# pcb_v2_3.net
KiCad netlist of a schematic drawn in EAGLE
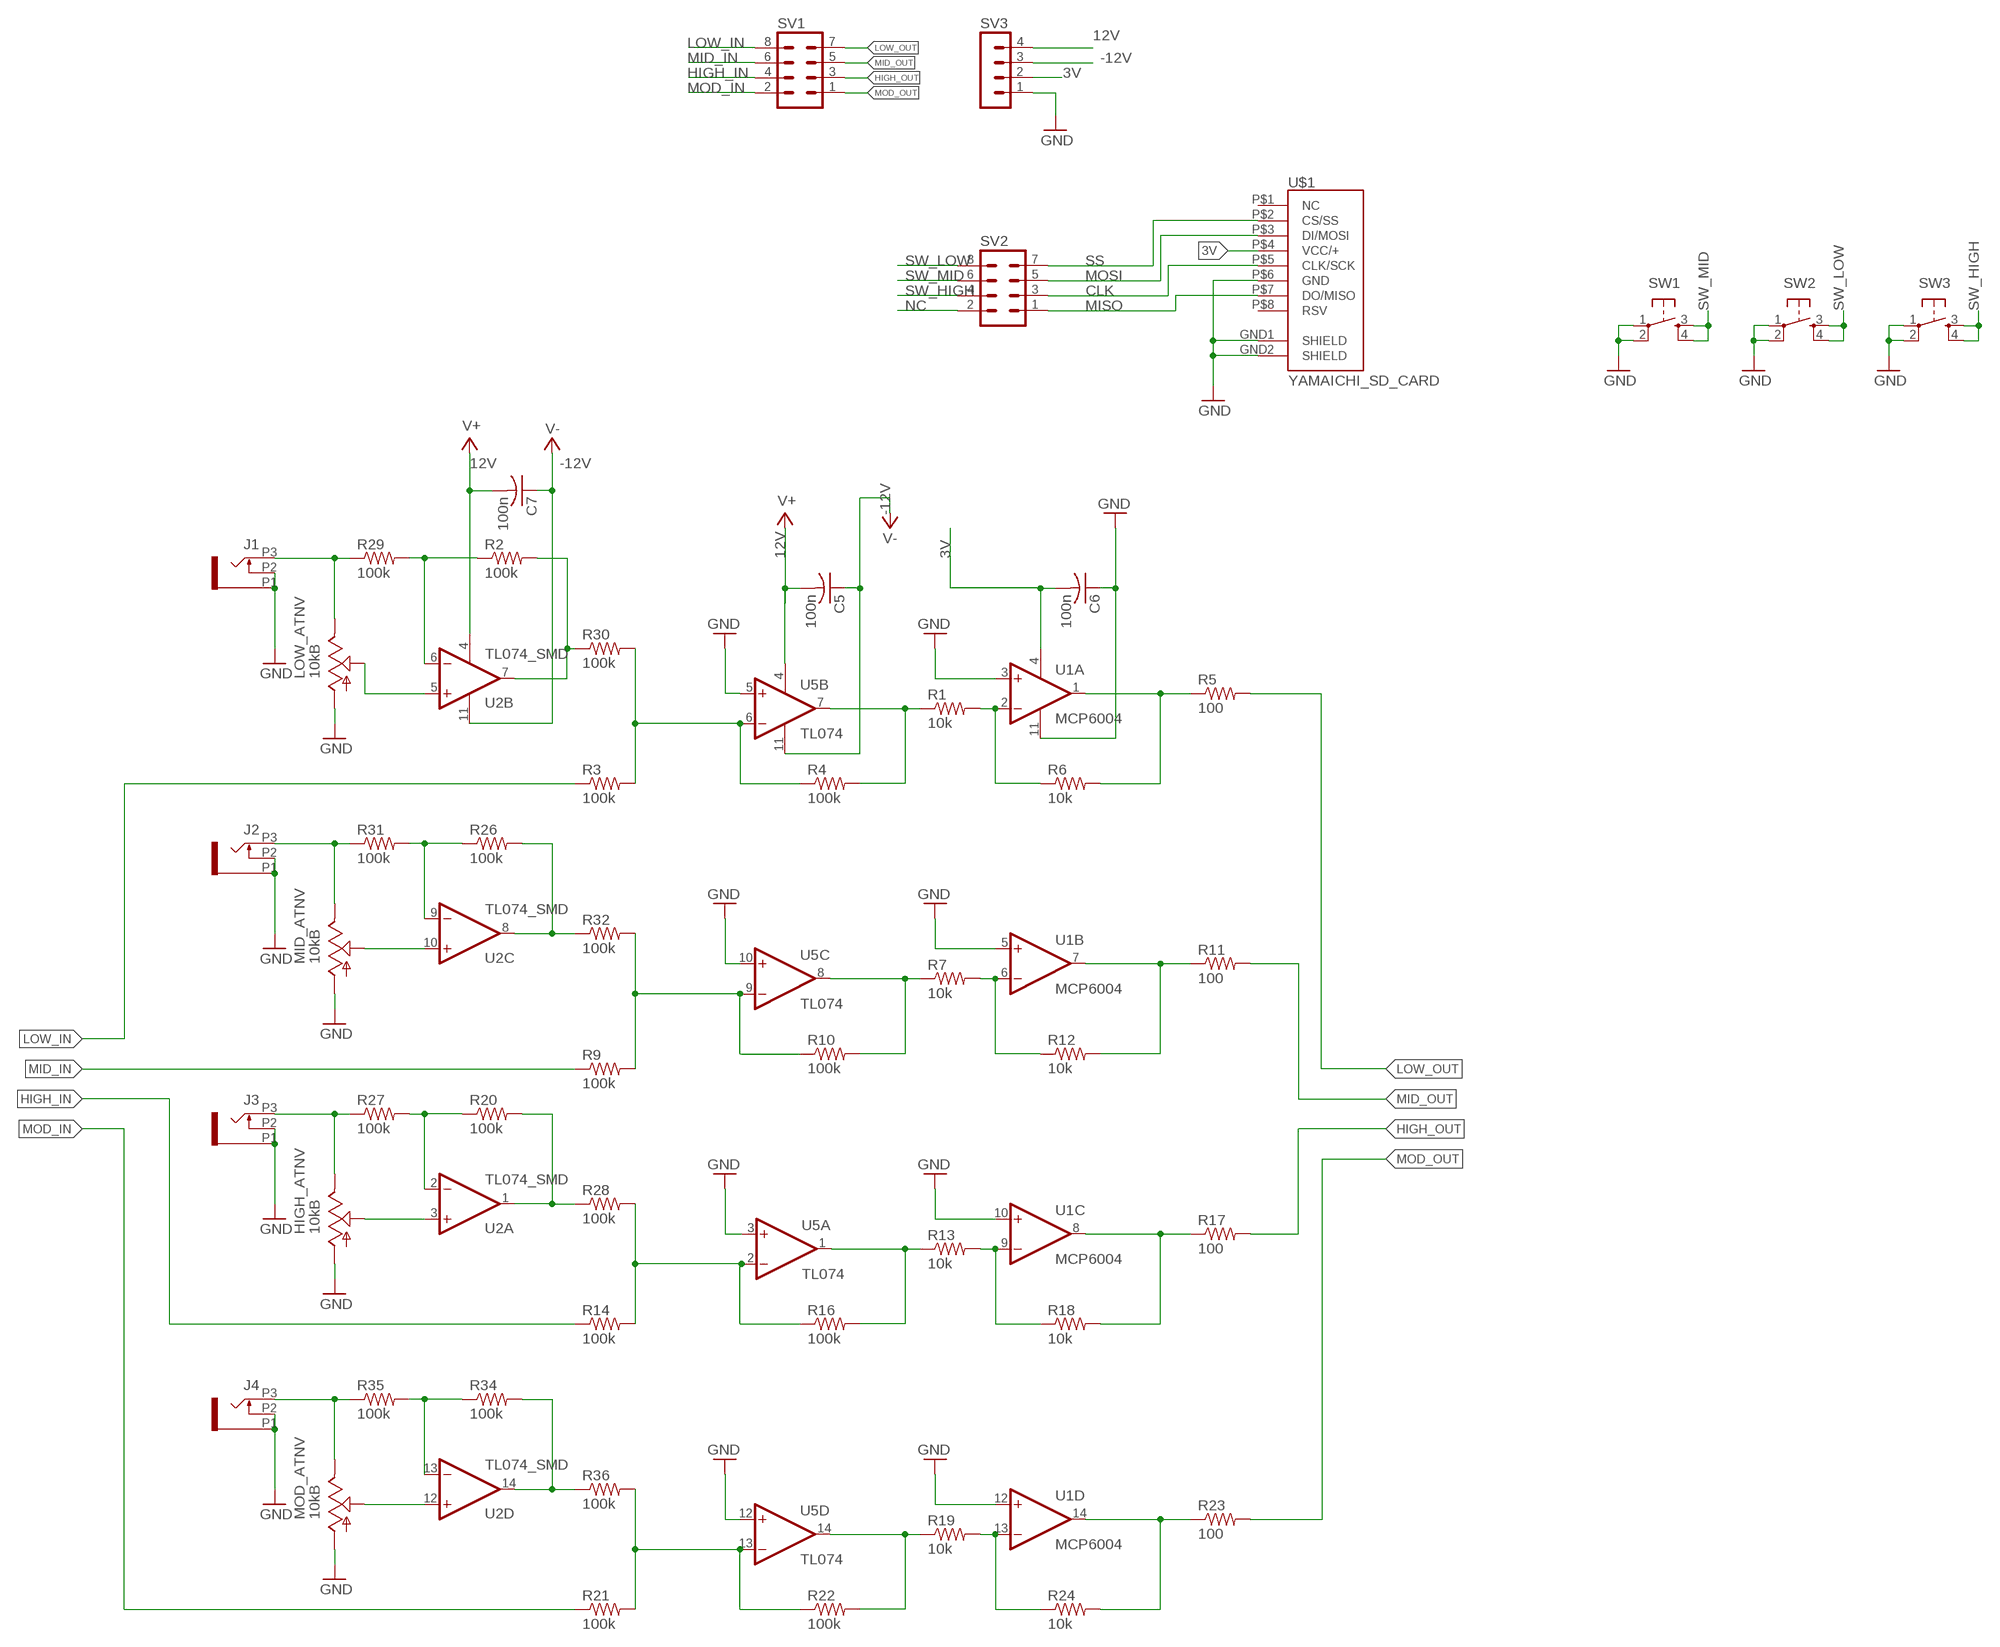
[diagram p0: schematic, sheet 1]

(export (version "E")
  (design (tool "Eeschema 10.0.6"))
  (components
    (comp (ref "C5")
      (value "100n")
      (footprint "eagle-import:C0603")
      (fields (field (name "SPICEPREFIX") "C"))
      (libsource (lib "eagle-import") (part "C-USC0603"))
    )
    (comp (ref "C6")
      (value "100n")
      (footprint "eagle-import:C0603")
      (fields (field (name "SPICEPREFIX") "C"))
      (libsource (lib "eagle-import") (part "C-USC0603"))
    )
    (comp (ref "C7")
      (value "100n")
      (footprint "eagle-import:C0603")
      (fields (field (name "SPICEPREFIX") "C"))
      (libsource (lib "eagle-import") (part "C-USC0603"))
    )
    (comp (ref "HIGH_ATNV")
      (value "10kB")
      (footprint "eagle-import:ALPS_POT_VERTICAL")
      (libsource (lib "eagle-import") (part "POT_USVERTICAL"))
    )
    (comp (ref "J1")
      (value "PJ301_THONKICONN6")
      (footprint "eagle-import:WQP_PJ_301M6")
      (fields (field (name "SPICEPREFIX") "J"))
      (libsource (lib "eagle-import") (part "PJ301_THONKICONN6"))
    )
    (comp (ref "J2")
      (value "PJ301_THONKICONN6")
      (footprint "eagle-import:WQP_PJ_301M6")
      (fields (field (name "SPICEPREFIX") "J"))
      (libsource (lib "eagle-import") (part "PJ301_THONKICONN6"))
    )
    (comp (ref "J3")
      (value "PJ301_THONKICONN6")
      (footprint "eagle-import:WQP_PJ_301M6")
      (fields (field (name "SPICEPREFIX") "J"))
      (libsource (lib "eagle-import") (part "PJ301_THONKICONN6"))
    )
    (comp (ref "J4")
      (value "PJ301_THONKICONN6")
      (footprint "eagle-import:WQP_PJ_301M6")
      (fields (field (name "SPICEPREFIX") "J"))
      (libsource (lib "eagle-import") (part "PJ301_THONKICONN6"))
    )
    (comp (ref "LOW_ATNV")
      (value "10kB")
      (footprint "eagle-import:ALPS_POT_VERTICAL")
      (libsource (lib "eagle-import") (part "POT_USVERTICAL"))
    )
    (comp (ref "MID_ATNV")
      (value "10kB")
      (footprint "eagle-import:ALPS_POT_VERTICAL")
      (libsource (lib "eagle-import") (part "POT_USVERTICAL"))
    )
    (comp (ref "MOD_ATNV")
      (value "10kB")
      (footprint "eagle-import:ALPS_POT_VERTICAL")
      (libsource (lib "eagle-import") (part "POT_USVERTICAL"))
    )
    (comp (ref "R1")
      (value "10k")
      (footprint "eagle-import:R0603")
      (fields (field (name "SPICEPREFIX") "R"))
      (libsource (lib "eagle-import") (part "R-US_R0603"))
    )
    (comp (ref "R2")
      (value "100k")
      (footprint "eagle-import:R0603")
      (fields (field (name "SPICEPREFIX") "R"))
      (libsource (lib "eagle-import") (part "R-US_R0603"))
    )
    (comp (ref "R3")
      (value "100k")
      (footprint "eagle-import:R0603")
      (fields (field (name "SPICEPREFIX") "R"))
      (libsource (lib "eagle-import") (part "R-US_R0603"))
    )
    (comp (ref "R4")
      (value "100k")
      (footprint "eagle-import:R0603")
      (fields (field (name "SPICEPREFIX") "R"))
      (libsource (lib "eagle-import") (part "R-US_R0603"))
    )
    (comp (ref "R5")
      (value "100")
      (footprint "eagle-import:R0603")
      (fields (field (name "SPICEPREFIX") "R"))
      (libsource (lib "eagle-import") (part "R-US_R0603"))
    )
    (comp (ref "R6")
      (value "10k")
      (footprint "eagle-import:R0603")
      (fields (field (name "SPICEPREFIX") "R"))
      (libsource (lib "eagle-import") (part "R-US_R0603"))
    )
    (comp (ref "R7")
      (value "10k")
      (footprint "eagle-import:R0603")
      (fields (field (name "SPICEPREFIX") "R"))
      (libsource (lib "eagle-import") (part "R-US_R0603"))
    )
    (comp (ref "R9")
      (value "100k")
      (footprint "eagle-import:R0603")
      (fields (field (name "SPICEPREFIX") "R"))
      (libsource (lib "eagle-import") (part "R-US_R0603"))
    )
    (comp (ref "R10")
      (value "100k")
      (footprint "eagle-import:R0603")
      (fields (field (name "SPICEPREFIX") "R"))
      (libsource (lib "eagle-import") (part "R-US_R0603"))
    )
    (comp (ref "R11")
      (value "100")
      (footprint "eagle-import:R0603")
      (fields (field (name "SPICEPREFIX") "R"))
      (libsource (lib "eagle-import") (part "R-US_R0603"))
    )
    (comp (ref "R12")
      (value "10k")
      (footprint "eagle-import:R0603")
      (fields (field (name "SPICEPREFIX") "R"))
      (libsource (lib "eagle-import") (part "R-US_R0603"))
    )
    (comp (ref "R13")
      (value "10k")
      (footprint "eagle-import:R0603")
      (fields (field (name "SPICEPREFIX") "R"))
      (libsource (lib "eagle-import") (part "R-US_R0603"))
    )
    (comp (ref "R14")
      (value "100k")
      (footprint "eagle-import:R0603")
      (fields (field (name "SPICEPREFIX") "R"))
      (libsource (lib "eagle-import") (part "R-US_R0603"))
    )
    (comp (ref "R16")
      (value "100k")
      (footprint "eagle-import:R0603")
      (fields (field (name "SPICEPREFIX") "R"))
      (libsource (lib "eagle-import") (part "R-US_R0603"))
    )
    (comp (ref "R17")
      (value "100")
      (footprint "eagle-import:R0603")
      (fields (field (name "SPICEPREFIX") "R"))
      (libsource (lib "eagle-import") (part "R-US_R0603"))
    )
    (comp (ref "R18")
      (value "10k")
      (footprint "eagle-import:R0603")
      (fields (field (name "SPICEPREFIX") "R"))
      (libsource (lib "eagle-import") (part "R-US_R0603"))
    )
    (comp (ref "R19")
      (value "10k")
      (footprint "eagle-import:R0603")
      (fields (field (name "SPICEPREFIX") "R"))
      (libsource (lib "eagle-import") (part "R-US_R0603"))
    )
    (comp (ref "R20")
      (value "100k")
      (footprint "eagle-import:R0603")
      (fields (field (name "SPICEPREFIX") "R"))
      (libsource (lib "eagle-import") (part "R-US_R0603"))
    )
    (comp (ref "R21")
      (value "100k")
      (footprint "eagle-import:R0603")
      (fields (field (name "SPICEPREFIX") "R"))
      (libsource (lib "eagle-import") (part "R-US_R0603"))
    )
    (comp (ref "R22")
      (value "100k")
      (footprint "eagle-import:R0603")
      (fields (field (name "SPICEPREFIX") "R"))
      (libsource (lib "eagle-import") (part "R-US_R0603"))
    )
    (comp (ref "R23")
      (value "100")
      (footprint "eagle-import:R0603")
      (fields (field (name "SPICEPREFIX") "R"))
      (libsource (lib "eagle-import") (part "R-US_R0603"))
    )
    (comp (ref "R24")
      (value "10k")
      (footprint "eagle-import:R0603")
      (fields (field (name "SPICEPREFIX") "R"))
      (libsource (lib "eagle-import") (part "R-US_R0603"))
    )
    (comp (ref "R26")
      (value "100k")
      (footprint "eagle-import:R0603")
      (fields (field (name "SPICEPREFIX") "R"))
      (libsource (lib "eagle-import") (part "R-US_R0603"))
    )
    (comp (ref "R27")
      (value "100k")
      (footprint "eagle-import:R0603")
      (fields (field (name "SPICEPREFIX") "R"))
      (libsource (lib "eagle-import") (part "R-US_R0603"))
    )
    (comp (ref "R28")
      (value "100k")
      (footprint "eagle-import:R0603")
      (fields (field (name "SPICEPREFIX") "R"))
      (libsource (lib "eagle-import") (part "R-US_R0603"))
    )
    (comp (ref "R29")
      (value "100k")
      (footprint "eagle-import:R0603")
      (fields (field (name "SPICEPREFIX") "R"))
      (libsource (lib "eagle-import") (part "R-US_R0603"))
    )
    (comp (ref "R30")
      (value "100k")
      (footprint "eagle-import:R0603")
      (fields (field (name "SPICEPREFIX") "R"))
      (libsource (lib "eagle-import") (part "R-US_R0603"))
    )
    (comp (ref "R31")
      (value "100k")
      (footprint "eagle-import:R0603")
      (fields (field (name "SPICEPREFIX") "R"))
      (libsource (lib "eagle-import") (part "R-US_R0603"))
    )
    (comp (ref "R32")
      (value "100k")
      (footprint "eagle-import:R0603")
      (fields (field (name "SPICEPREFIX") "R"))
      (libsource (lib "eagle-import") (part "R-US_R0603"))
    )
    (comp (ref "R34")
      (value "100k")
      (footprint "eagle-import:R0603")
      (fields (field (name "SPICEPREFIX") "R"))
      (libsource (lib "eagle-import") (part "R-US_R0603"))
    )
    (comp (ref "R35")
      (value "100k")
      (footprint "eagle-import:R0603")
      (fields (field (name "SPICEPREFIX") "R"))
      (libsource (lib "eagle-import") (part "R-US_R0603"))
    )
    (comp (ref "R36")
      (value "100k")
      (footprint "eagle-import:R0603")
      (fields (field (name "SPICEPREFIX") "R"))
      (libsource (lib "eagle-import") (part "R-US_R0603"))
    )
    (comp (ref "SV1")
      (value "MA04-2")
      (footprint "eagle-import:MA04-2")
      (libsource (lib "eagle-import") (part "MA04-2"))
    )
    (comp (ref "SV2")
      (value "MA04-2")
      (footprint "eagle-import:MA04-2")
      (libsource (lib "eagle-import") (part "MA04-2"))
    )
    (comp (ref "SV3")
      (value "MA04-1")
      (footprint "eagle-import:MA04-1")
      (libsource (lib "eagle-import") (part "MA04-1"))
    )
    (comp (ref "SW1")
      (value "TAC_SWITCHPTH")
      (footprint "eagle-import:TACTILE-PTH")
      (libsource (lib "eagle-import") (part "TAC_SWITCHPTH"))
    )
    (comp (ref "SW2")
      (value "TAC_SWITCHPTH")
      (footprint "eagle-import:TACTILE-PTH")
      (libsource (lib "eagle-import") (part "TAC_SWITCHPTH"))
    )
    (comp (ref "SW3")
      (value "TAC_SWITCHPTH")
      (footprint "eagle-import:TACTILE-PTH")
      (libsource (lib "eagle-import") (part "TAC_SWITCHPTH"))
    )
    (comp (ref "U$1")
      (value "YAMAICHI_SD_CARD")
      (footprint "eagle-import:YAMAICHI_MICROSD_VERTICAL")
      (libsource (lib "eagle-import") (part "YAMAICHI_SD_CARD"))
    )
    (comp (ref "U1")
      (value "MCP6004")
      (footprint "eagle-import:SO14")
      (libsource (lib "eagle-import") (part "MCP6004_SMD"))
    )
    (comp (ref "U2")
      (value "TL074_SMD")
      (footprint "eagle-import:SO14")
      (libsource (lib "eagle-import") (part "TL074_SMD"))
    )
    (comp (ref "U5")
      (value "TL074")
      (footprint "eagle-import:SO14")
      (libsource (lib "eagle-import") (part "TL074_SMD"))
    )
  )
  (nets
    (net (code "1") (name "/CLK") (class "Default")
      (node (ref "SV2") (pin "3") (pinfunction "3_3") (pintype "passive"))
      (node (ref "U$1") (pin "P$5") (pinfunction "CLK/SCK_P$5") (pintype "bidirectional"))
    )
    (net (code "2") (name "/MISO") (class "Default")
      (node (ref "SV2") (pin "1") (pinfunction "1_1") (pintype "passive"))
      (node (ref "U$1") (pin "P$7") (pinfunction "DO/MISO_P$7") (pintype "bidirectional"))
    )
    (net (code "3") (name "/MOSI") (class "Default")
      (node (ref "SV2") (pin "5") (pinfunction "5_5") (pintype "passive"))
      (node (ref "U$1") (pin "P$3") (pinfunction "DI/MOSI_P$3") (pintype "bidirectional"))
    )
    (net (code "4") (name "/NC") (class "Default")
      (node (ref "SV2") (pin "2") (pinfunction "2_2") (pintype "passive"))
    )
    (net (code "5") (name "/SS") (class "Default")
      (node (ref "SV2") (pin "7") (pinfunction "7_7") (pintype "passive"))
      (node (ref "U$1") (pin "P$2") (pinfunction "CS/SS_P$2") (pintype "bidirectional"))
    )
    (net (code "6") (name "/SW_HIGH") (class "Default")
      (node (ref "SV2") (pin "4") (pinfunction "4_4") (pintype "passive"))
      (node (ref "SW3") (pin "3") (pinfunction "3_3") (pintype "passive"))
      (node (ref "SW3") (pin "4") (pinfunction "4_4") (pintype "passive"))
    )
    (net (code "7") (name "/SW_LOW") (class "Default")
      (node (ref "SV2") (pin "8") (pinfunction "8_8") (pintype "passive"))
      (node (ref "SW2") (pin "3") (pinfunction "3_3") (pintype "passive"))
      (node (ref "SW2") (pin "4") (pinfunction "4_4") (pintype "passive"))
    )
    (net (code "8") (name "/SW_MID") (class "Default")
      (node (ref "SV2") (pin "6") (pinfunction "6_6") (pintype "passive"))
      (node (ref "SW1") (pin "3") (pinfunction "3_3") (pintype "passive"))
      (node (ref "SW1") (pin "4") (pinfunction "4_4") (pintype "passive"))
    )
    (net (code "9") (name "3V") (class "Default")
      (node (ref "C6") (pin "2") (pinfunction "2_2") (pintype "passive"))
      (node (ref "SV3") (pin "2") (pinfunction "2_2") (pintype "passive"))
      (node (ref "U$1") (pin "P$4") (pinfunction "VCC/+_P$4") (pintype "bidirectional"))
      (node (ref "U1") (pin "4") (pinfunction "V+_4") (pintype "power_in"))
    )
    (net (code "10") (name "GND") (class "Default")
      (node (ref "C6") (pin "1") (pinfunction "1_1") (pintype "passive"))
      (node (ref "HIGH_ATNV") (pin "P$3") (pinfunction "A_P$3") (pintype "passive"))
      (node (ref "J1") (pin "P1") (pinfunction "1_P1") (pintype "passive"))
      (node (ref "J1") (pin "P2") (pinfunction "2_P2") (pintype "passive"))
      (node (ref "J2") (pin "P1") (pinfunction "1_P1") (pintype "passive"))
      (node (ref "J2") (pin "P2") (pinfunction "2_P2") (pintype "passive"))
      (node (ref "J3") (pin "P1") (pinfunction "1_P1") (pintype "passive"))
      (node (ref "J3") (pin "P2") (pinfunction "2_P2") (pintype "passive"))
      (node (ref "J4") (pin "P1") (pinfunction "1_P1") (pintype "passive"))
      (node (ref "J4") (pin "P2") (pinfunction "2_P2") (pintype "passive"))
      (node (ref "LOW_ATNV") (pin "P$3") (pinfunction "A_P$3") (pintype "passive"))
      (node (ref "MID_ATNV") (pin "P$3") (pinfunction "A_P$3") (pintype "passive"))
      (node (ref "MOD_ATNV") (pin "P$3") (pinfunction "A_P$3") (pintype "passive"))
      (node (ref "SV3") (pin "1") (pinfunction "1_1") (pintype "passive"))
      (node (ref "SW1") (pin "1") (pinfunction "1_1") (pintype "passive"))
      (node (ref "SW1") (pin "2") (pinfunction "2_2") (pintype "passive"))
      (node (ref "SW2") (pin "1") (pinfunction "1_1") (pintype "passive"))
      (node (ref "SW2") (pin "2") (pinfunction "2_2") (pintype "passive"))
      (node (ref "SW3") (pin "1") (pinfunction "1_1") (pintype "passive"))
      (node (ref "SW3") (pin "2") (pinfunction "2_2") (pintype "passive"))
      (node (ref "U$1") (pin "GND1") (pinfunction "SHIELD_GND1") (pintype "bidirectional"))
      (node (ref "U$1") (pin "GND2") (pinfunction "SHIELD_GND2") (pintype "bidirectional"))
      (node (ref "U$1") (pin "P$6") (pinfunction "GND_P$6") (pintype "bidirectional"))
      (node (ref "U1") (pin "10") (pinfunction "+IN_10") (pintype "input"))
      (node (ref "U1") (pin "11") (pinfunction "V-_11") (pintype "power_in"))
      (node (ref "U1") (pin "12") (pinfunction "+IN_12") (pintype "input"))
      (node (ref "U1") (pin "3") (pinfunction "+IN_3") (pintype "input"))
      (node (ref "U1") (pin "5") (pinfunction "+IN_5") (pintype "input"))
      (node (ref "U5") (pin "10") (pinfunction "+IN_10") (pintype "input"))
      (node (ref "U5") (pin "12") (pinfunction "+IN_12") (pintype "input"))
      (node (ref "U5") (pin "3") (pinfunction "+IN_3") (pintype "input"))
      (node (ref "U5") (pin "5") (pinfunction "+IN_5") (pintype "input"))
    )
    (net (code "11") (name "HIGH_IN") (class "Default")
      (node (ref "R14") (pin "1") (pinfunction "1_1") (pintype "passive"))
      (node (ref "SV1") (pin "4") (pinfunction "4_4") (pintype "passive"))
    )
    (net (code "12") (name "HIGH_OUT") (class "Default")
      (node (ref "R17") (pin "2") (pinfunction "2_2") (pintype "passive"))
      (node (ref "SV1") (pin "3") (pinfunction "3_3") (pintype "passive"))
    )
    (net (code "13") (name "LOW_IN") (class "Default")
      (node (ref "R3") (pin "1") (pinfunction "1_1") (pintype "passive"))
      (node (ref "SV1") (pin "8") (pinfunction "8_8") (pintype "passive"))
    )
    (net (code "14") (name "LOW_OUT") (class "Default")
      (node (ref "R5") (pin "2") (pinfunction "2_2") (pintype "passive"))
      (node (ref "SV1") (pin "7") (pinfunction "7_7") (pintype "passive"))
    )
    (net (code "15") (name "MID_IN") (class "Default")
      (node (ref "R9") (pin "1") (pinfunction "1_1") (pintype "passive"))
      (node (ref "SV1") (pin "6") (pinfunction "6_6") (pintype "passive"))
    )
    (net (code "16") (name "MID_OUT") (class "Default")
      (node (ref "R11") (pin "2") (pinfunction "2_2") (pintype "passive"))
      (node (ref "SV1") (pin "5") (pinfunction "5_5") (pintype "passive"))
    )
    (net (code "17") (name "MOD_IN") (class "Default")
      (node (ref "R21") (pin "1") (pinfunction "1_1") (pintype "passive"))
      (node (ref "SV1") (pin "2") (pinfunction "2_2") (pintype "passive"))
    )
    (net (code "18") (name "MOD_OUT") (class "Default")
      (node (ref "R23") (pin "2") (pinfunction "2_2") (pintype "passive"))
      (node (ref "SV1") (pin "1") (pinfunction "1_1") (pintype "passive"))
    )
    (net (code "19") (name "Net-(HIGH_ATNV-E)") (class "Default")
      (node (ref "HIGH_ATNV") (pin "P$1") (pinfunction "E_P$1") (pintype "passive"))
      (node (ref "J3") (pin "P3") (pinfunction "3_P3") (pintype "passive"))
      (node (ref "R27") (pin "1") (pinfunction "1_1") (pintype "passive"))
    )
    (net (code "20") (name "Net-(HIGH_ATNV-S)") (class "Default")
      (node (ref "HIGH_ATNV") (pin "P$2") (pinfunction "S_P$2") (pintype "passive"))
      (node (ref "U2") (pin "3") (pinfunction "+IN_3") (pintype "input"))
    )
    (net (code "21") (name "Net-(J1-3)") (class "Default")
      (node (ref "J1") (pin "P3") (pinfunction "3_P3") (pintype "passive"))
      (node (ref "LOW_ATNV") (pin "P$1") (pinfunction "E_P$1") (pintype "passive"))
      (node (ref "R29") (pin "1") (pinfunction "1_1") (pintype "passive"))
    )
    (net (code "22") (name "Net-(J2-3)") (class "Default")
      (node (ref "J2") (pin "P3") (pinfunction "3_P3") (pintype "passive"))
      (node (ref "MID_ATNV") (pin "P$1") (pinfunction "E_P$1") (pintype "passive"))
      (node (ref "R31") (pin "1") (pinfunction "1_1") (pintype "passive"))
    )
    (net (code "23") (name "Net-(J4-3)") (class "Default")
      (node (ref "J4") (pin "P3") (pinfunction "3_P3") (pintype "passive"))
      (node (ref "MOD_ATNV") (pin "P$1") (pinfunction "E_P$1") (pintype "passive"))
      (node (ref "R35") (pin "1") (pinfunction "1_1") (pintype "passive"))
    )
    (net (code "24") (name "Net-(LOW_ATNV-S)") (class "Default")
      (node (ref "LOW_ATNV") (pin "P$2") (pinfunction "S_P$2") (pintype "passive"))
      (node (ref "U2") (pin "5") (pinfunction "+IN_5") (pintype "input"))
    )
    (net (code "25") (name "Net-(MID_ATNV-S)") (class "Default")
      (node (ref "MID_ATNV") (pin "P$2") (pinfunction "S_P$2") (pintype "passive"))
      (node (ref "U2") (pin "10") (pinfunction "+IN_10") (pintype "input"))
    )
    (net (code "26") (name "Net-(MOD_ATNV-S)") (class "Default")
      (node (ref "MOD_ATNV") (pin "P$2") (pinfunction "S_P$2") (pintype "passive"))
      (node (ref "U2") (pin "12") (pinfunction "+IN_12") (pintype "input"))
    )
    (net (code "27") (name "Net-(U1A--IN)") (class "Default")
      (node (ref "R1") (pin "2") (pinfunction "2_2") (pintype "passive"))
      (node (ref "R6") (pin "1") (pinfunction "1_1") (pintype "passive"))
      (node (ref "U1") (pin "2") (pinfunction "-IN_2") (pintype "input"))
    )
    (net (code "28") (name "Net-(U1A-OUT)") (class "Default")
      (node (ref "R5") (pin "1") (pinfunction "1_1") (pintype "passive"))
      (node (ref "R6") (pin "2") (pinfunction "2_2") (pintype "passive"))
      (node (ref "U1") (pin "1") (pinfunction "OUT_1") (pintype "output"))
    )
    (net (code "29") (name "Net-(U1B--IN)") (class "Default")
      (node (ref "R12") (pin "1") (pinfunction "1_1") (pintype "passive"))
      (node (ref "R7") (pin "2") (pinfunction "2_2") (pintype "passive"))
      (node (ref "U1") (pin "6") (pinfunction "-IN_6") (pintype "input"))
    )
    (net (code "30") (name "Net-(U1B-OUT)") (class "Default")
      (node (ref "R11") (pin "1") (pinfunction "1_1") (pintype "passive"))
      (node (ref "R12") (pin "2") (pinfunction "2_2") (pintype "passive"))
      (node (ref "U1") (pin "7") (pinfunction "OUT_7") (pintype "output"))
    )
    (net (code "31") (name "Net-(U1C--IN)") (class "Default")
      (node (ref "R13") (pin "2") (pinfunction "2_2") (pintype "passive"))
      (node (ref "R18") (pin "1") (pinfunction "1_1") (pintype "passive"))
      (node (ref "U1") (pin "9") (pinfunction "-IN_9") (pintype "input"))
    )
    (net (code "32") (name "Net-(U1C-OUT)") (class "Default")
      (node (ref "R17") (pin "1") (pinfunction "1_1") (pintype "passive"))
      (node (ref "R18") (pin "2") (pinfunction "2_2") (pintype "passive"))
      (node (ref "U1") (pin "8") (pinfunction "OUT_8") (pintype "output"))
    )
    (net (code "33") (name "Net-(U1D--IN)") (class "Default")
      (node (ref "R19") (pin "2") (pinfunction "2_2") (pintype "passive"))
      (node (ref "R24") (pin "1") (pinfunction "1_1") (pintype "passive"))
      (node (ref "U1") (pin "13") (pinfunction "-IN_13") (pintype "input"))
    )
    (net (code "34") (name "Net-(U1D-OUT)") (class "Default")
      (node (ref "R23") (pin "1") (pinfunction "1_1") (pintype "passive"))
      (node (ref "R24") (pin "2") (pinfunction "2_2") (pintype "passive"))
      (node (ref "U1") (pin "14") (pinfunction "OUT_14") (pintype "output"))
    )
    (net (code "35") (name "Net-(U2A--IN)") (class "Default")
      (node (ref "R20") (pin "1") (pinfunction "1_1") (pintype "passive"))
      (node (ref "R27") (pin "2") (pinfunction "2_2") (pintype "passive"))
      (node (ref "U2") (pin "2") (pinfunction "-IN_2") (pintype "input"))
    )
    (net (code "36") (name "Net-(U2A-OUT)") (class "Default")
      (node (ref "R20") (pin "2") (pinfunction "2_2") (pintype "passive"))
      (node (ref "R28") (pin "1") (pinfunction "1_1") (pintype "passive"))
      (node (ref "U2") (pin "1") (pinfunction "OUT_1") (pintype "output"))
    )
    (net (code "37") (name "Net-(U2B--IN)") (class "Default")
      (node (ref "R2") (pin "1") (pinfunction "1_1") (pintype "passive"))
      (node (ref "R29") (pin "2") (pinfunction "2_2") (pintype "passive"))
      (node (ref "U2") (pin "6") (pinfunction "-IN_6") (pintype "input"))
    )
    (net (code "38") (name "Net-(U2B-OUT)") (class "Default")
      (node (ref "R2") (pin "2") (pinfunction "2_2") (pintype "passive"))
      (node (ref "R30") (pin "1") (pinfunction "1_1") (pintype "passive"))
      (node (ref "U2") (pin "7") (pinfunction "OUT_7") (pintype "output"))
    )
    (net (code "39") (name "Net-(U2C--IN)") (class "Default")
      (node (ref "R26") (pin "1") (pinfunction "1_1") (pintype "passive"))
      (node (ref "R31") (pin "2") (pinfunction "2_2") (pintype "passive"))
      (node (ref "U2") (pin "9") (pinfunction "-IN_9") (pintype "input"))
    )
    (net (code "40") (name "Net-(U2C-OUT)") (class "Default")
      (node (ref "R26") (pin "2") (pinfunction "2_2") (pintype "passive"))
      (node (ref "R32") (pin "1") (pinfunction "1_1") (pintype "passive"))
      (node (ref "U2") (pin "8") (pinfunction "OUT_8") (pintype "output"))
    )
    (net (code "41") (name "Net-(U2D--IN)") (class "Default")
      (node (ref "R34") (pin "1") (pinfunction "1_1") (pintype "passive"))
      (node (ref "R35") (pin "2") (pinfunction "2_2") (pintype "passive"))
      (node (ref "U2") (pin "13") (pinfunction "-IN_13") (pintype "input"))
    )
    (net (code "42") (name "Net-(U2D-OUT)") (class "Default")
      (node (ref "R34") (pin "2") (pinfunction "2_2") (pintype "passive"))
      (node (ref "R36") (pin "1") (pinfunction "1_1") (pintype "passive"))
      (node (ref "U2") (pin "14") (pinfunction "OUT_14") (pintype "output"))
    )
    (net (code "43") (name "Net-(U5A--IN)") (class "Default")
      (node (ref "R14") (pin "2") (pinfunction "2_2") (pintype "passive"))
      (node (ref "R16") (pin "1") (pinfunction "1_1") (pintype "passive"))
      (node (ref "R28") (pin "2") (pinfunction "2_2") (pintype "passive"))
      (node (ref "U5") (pin "2") (pinfunction "-IN_2") (pintype "input"))
    )
    (net (code "44") (name "Net-(U5A-OUT)") (class "Default")
      (node (ref "R13") (pin "1") (pinfunction "1_1") (pintype "passive"))
      (node (ref "R16") (pin "2") (pinfunction "2_2") (pintype "passive"))
      (node (ref "U5") (pin "1") (pinfunction "OUT_1") (pintype "output"))
    )
    (net (code "45") (name "Net-(U5B--IN)") (class "Default")
      (node (ref "R3") (pin "2") (pinfunction "2_2") (pintype "passive"))
      (node (ref "R30") (pin "2") (pinfunction "2_2") (pintype "passive"))
      (node (ref "R4") (pin "1") (pinfunction "1_1") (pintype "passive"))
      (node (ref "U5") (pin "6") (pinfunction "-IN_6") (pintype "input"))
    )
    (net (code "46") (name "Net-(U5B-OUT)") (class "Default")
      (node (ref "R1") (pin "1") (pinfunction "1_1") (pintype "passive"))
      (node (ref "R4") (pin "2") (pinfunction "2_2") (pintype "passive"))
      (node (ref "U5") (pin "7") (pinfunction "OUT_7") (pintype "output"))
    )
    (net (code "47") (name "Net-(U5C--IN)") (class "Default")
      (node (ref "R10") (pin "1") (pinfunction "1_1") (pintype "passive"))
      (node (ref "R32") (pin "2") (pinfunction "2_2") (pintype "passive"))
      (node (ref "R9") (pin "2") (pinfunction "2_2") (pintype "passive"))
      (node (ref "U5") (pin "9") (pinfunction "-IN_9") (pintype "input"))
    )
    (net (code "48") (name "Net-(U5C-OUT)") (class "Default")
      (node (ref "R10") (pin "2") (pinfunction "2_2") (pintype "passive"))
      (node (ref "R7") (pin "1") (pinfunction "1_1") (pintype "passive"))
      (node (ref "U5") (pin "8") (pinfunction "OUT_8") (pintype "output"))
    )
    (net (code "49") (name "Net-(U5D--IN)") (class "Default")
      (node (ref "R21") (pin "2") (pinfunction "2_2") (pintype "passive"))
      (node (ref "R22") (pin "1") (pinfunction "1_1") (pintype "passive"))
      (node (ref "R36") (pin "2") (pinfunction "2_2") (pintype "passive"))
      (node (ref "U5") (pin "13") (pinfunction "-IN_13") (pintype "input"))
    )
    (net (code "50") (name "Net-(U5D-OUT)") (class "Default")
      (node (ref "R19") (pin "1") (pinfunction "1_1") (pintype "passive"))
      (node (ref "R22") (pin "2") (pinfunction "2_2") (pintype "passive"))
      (node (ref "U5") (pin "14") (pinfunction "OUT_14") (pintype "output"))
    )
    (net (code "51") (name "V+") (class "Default")
      (node (ref "C5") (pin "2") (pinfunction "2_2") (pintype "passive"))
      (node (ref "C7") (pin "2") (pinfunction "2_2") (pintype "passive"))
      (node (ref "SV3") (pin "4") (pinfunction "4_4") (pintype "passive"))
      (node (ref "U2") (pin "4") (pinfunction "V+_4") (pintype "power_in"))
      (node (ref "U5") (pin "4") (pinfunction "V+_4") (pintype "power_in"))
    )
    (net (code "52") (name "V-") (class "Default")
      (node (ref "C5") (pin "1") (pinfunction "1_1") (pintype "passive"))
      (node (ref "C7") (pin "1") (pinfunction "1_1") (pintype "passive"))
      (node (ref "SV3") (pin "3") (pinfunction "3_3") (pintype "passive"))
      (node (ref "U2") (pin "11") (pinfunction "V-_11") (pintype "power_in"))
      (node (ref "U5") (pin "11") (pinfunction "V-_11") (pintype "power_in"))
    )
    (net (code "53") (name "unconnected-(U$1-NC-PadP$1)") (class "Default")
      (node (ref "U$1") (pin "P$1") (pinfunction "NC_P$1") (pintype "bidirectional"))
    )
    (net (code "54") (name "unconnected-(U$1-RSV-PadP$8)") (class "Default")
      (node (ref "U$1") (pin "P$8") (pinfunction "RSV_P$8") (pintype "bidirectional"))
    )
  )
)
